# breakout_STM32F030F4P6.net
KiCad netlist of a schematic drawn in EAGLE
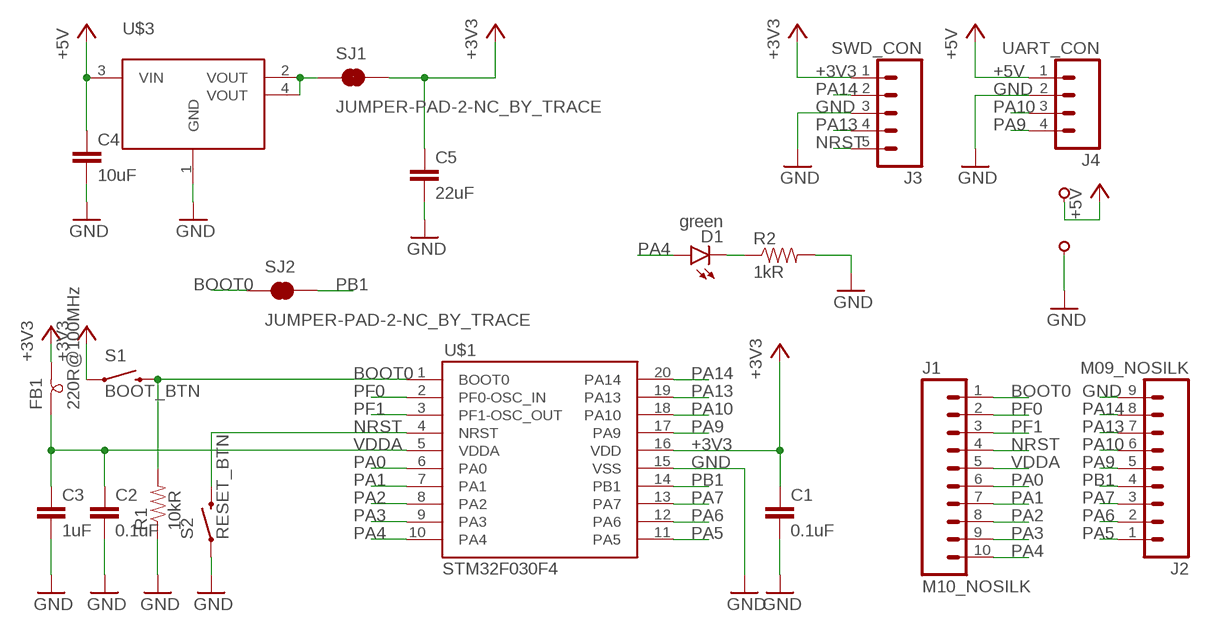
[diagram p0: schematic, sheet 1]

(export (version "E")
  (design (tool "Eeschema 10.0.6"))
  (components
    (comp (ref "C1")
      (value "0.1uF")
      (footprint "eagle-import:0805")
      (libsource (lib "eagle-import") (part "CAPACITOR0805"))
    )
    (comp (ref "C2")
      (value "0.1uF")
      (footprint "eagle-import:0805")
      (libsource (lib "eagle-import") (part "CAPACITOR0805"))
    )
    (comp (ref "C3")
      (value "1uF")
      (footprint "eagle-import:0805")
      (libsource (lib "eagle-import") (part "CAPACITOR0805"))
    )
    (comp (ref "C4")
      (value "10uF")
      (footprint "eagle-import:0805")
      (libsource (lib "eagle-import") (part "CAPACITOR0805"))
    )
    (comp (ref "C5")
      (value "22uF")
      (footprint "eagle-import:0805")
      (libsource (lib "eagle-import") (part "CAPACITOR0805"))
    )
    (comp (ref "D1")
      (value "green")
      (footprint "eagle-import:LED-805")
      (libsource (lib "eagle-import") (part "LED805"))
    )
    (comp (ref "FB1")
      (value "220R@100MHz")
      (footprint "eagle-import:0805")
      (libsource (lib "eagle-import") (part "FERRITE-BEAD0805"))
    )
    (comp (ref "J1")
      (value "M10_NOSILK")
      (footprint "eagle-import:M10_NOSILK")
      (libsource (lib "eagle-import") (part "M10_NOSILK"))
    )
    (comp (ref "J2")
      (value "M09_NOSILK")
      (footprint "eagle-import:M09_NOSILK")
      (libsource (lib "eagle-import") (part "M09_NOSILK"))
    )
    (comp (ref "J3")
      (value "SWD_CON")
      (footprint "eagle-import:M05_NOSILK_1SQ")
      (libsource (lib "eagle-import") (part "M05_NOSILK_1SQ"))
    )
    (comp (ref "J4")
      (value "UART_CON")
      (footprint "eagle-import:M04_NOSILK_1SQ")
      (libsource (lib "eagle-import") (part "M04_NOSILK_1SQ"))
    )
    (comp (ref "R1")
      (value "10kR")
      (footprint "eagle-import:0805")
      (libsource (lib "eagle-import") (part "RESISTOR0805"))
    )
    (comp (ref "R2")
      (value "1kR")
      (footprint "eagle-import:0805")
      (libsource (lib "eagle-import") (part "RESISTOR0805"))
    )
    (comp (ref "S1")
      (value "BOOT_BTN")
      (footprint "eagle-import:TACTILE-SWITCH-1101NE")
      (libsource (lib "eagle-import") (part "SWITCH-MOMENTARY-2-SMD-1101NE"))
    )
    (comp (ref "S2")
      (value "RESET_BTN")
      (footprint "eagle-import:TACTILE-SWITCH-1101NE")
      (libsource (lib "eagle-import") (part "SWITCH-MOMENTARY-2-SMD-1101NE"))
    )
    (comp (ref "SJ1")
      (value "JUMPER-PAD-2-NC_BY_TRACE")
      (footprint "eagle-import:PAD-JUMPER-2-NC_BY_TRACE_YES_SILK")
      (libsource (lib "eagle-import") (part "JUMPER-PAD-2-NC_BY_TRACE"))
    )
    (comp (ref "SJ2")
      (value "JUMPER-PAD-2-NC_BY_TRACE")
      (footprint "eagle-import:PAD-JUMPER-2-NC_BY_TRACE_YES_SILK")
      (libsource (lib "eagle-import") (part "JUMPER-PAD-2-NC_BY_TRACE"))
    )
    (comp (ref "U$1")
      (value "STM32F030F4")
      (footprint "eagle-import:TSSOP-20")
      (libsource (lib "eagle-import") (part "STM32F030F4"))
    )
    (comp (ref "U$2")
      (value "M01_1SQ")
      (footprint "eagle-import:M01_1SQ")
      (libsource (lib "eagle-import") (part "M01_1SQ"))
    )
    (comp (ref "U$3")
      (value "AMS1117_SOT223")
      (footprint "eagle-import:SOT223")
      (libsource (lib "eagle-import") (part "AMS1117_SOT223"))
    )
    (comp (ref "U$4")
      (value "M01_NOSILK")
      (footprint "eagle-import:M01_NOSILK")
      (libsource (lib "eagle-import") (part "M01_NOSILK"))
    )
  )
  (nets
    (net (code "1") (name "+3V3") (class "Default")
      (node (ref "C1") (pin "1") (pinfunction "1_1") (pintype "passive"))
      (node (ref "C5") (pin "1") (pinfunction "1_1") (pintype "passive"))
      (node (ref "FB1") (pin "2") (pinfunction "2_2") (pintype "passive"))
      (node (ref "J3") (pin "1") (pinfunction "1_1") (pintype "passive"))
      (node (ref "S1") (pin "1") (pinfunction "1_1") (pintype "passive"))
      (node (ref "SJ1") (pin "2") (pinfunction "2_2") (pintype "passive"))
      (node (ref "U$1") (pin "16") (pinfunction "VDD_16") (pintype "bidirectional"))
    )
    (net (code "2") (name "+5V") (class "Default")
      (node (ref "C4") (pin "1") (pinfunction "1_1") (pintype "passive"))
      (node (ref "J4") (pin "1") (pinfunction "1_1") (pintype "passive"))
      (node (ref "U$2") (pin "1") (pinfunction "1_1") (pintype "bidirectional"))
      (node (ref "U$3") (pin "3") (pinfunction "VIN_3") (pintype "bidirectional"))
    )
    (net (code "3") (name "/BOOT0") (class "Default")
      (node (ref "J1") (pin "1") (pinfunction "1_1") (pintype "passive"))
      (node (ref "R1") (pin "2") (pinfunction "2_2") (pintype "passive"))
      (node (ref "S1") (pin "2") (pinfunction "2_2") (pintype "passive"))
      (node (ref "SJ2") (pin "1") (pinfunction "1_1") (pintype "passive"))
      (node (ref "U$1") (pin "1") (pinfunction "BOOT0_1") (pintype "bidirectional"))
    )
    (net (code "4") (name "/NRST") (class "Default")
      (node (ref "J1") (pin "4") (pinfunction "4_4") (pintype "passive"))
      (node (ref "J3") (pin "5") (pinfunction "5_5") (pintype "passive"))
      (node (ref "S2") (pin "2") (pinfunction "2_2") (pintype "passive"))
      (node (ref "U$1") (pin "4") (pinfunction "NRST_4") (pintype "bidirectional"))
    )
    (net (code "5") (name "/PA0") (class "Default")
      (node (ref "J1") (pin "6") (pinfunction "6_6") (pintype "passive"))
      (node (ref "U$1") (pin "6") (pinfunction "PA0_6") (pintype "bidirectional"))
    )
    (net (code "6") (name "/PA1") (class "Default")
      (node (ref "J1") (pin "7") (pinfunction "7_7") (pintype "passive"))
      (node (ref "U$1") (pin "7") (pinfunction "PA1_7") (pintype "bidirectional"))
    )
    (net (code "7") (name "/PA2") (class "Default")
      (node (ref "J1") (pin "8") (pinfunction "8_8") (pintype "passive"))
      (node (ref "U$1") (pin "8") (pinfunction "PA2_8") (pintype "bidirectional"))
    )
    (net (code "8") (name "/PA3") (class "Default")
      (node (ref "J1") (pin "9") (pinfunction "9_9") (pintype "passive"))
      (node (ref "U$1") (pin "9") (pinfunction "PA3_9") (pintype "bidirectional"))
    )
    (net (code "9") (name "/PA4") (class "Default")
      (node (ref "D1") (pin "A") (pinfunction "A_A") (pintype "passive"))
      (node (ref "J1") (pin "10") (pinfunction "10_10") (pintype "passive"))
      (node (ref "U$1") (pin "10") (pinfunction "PA4_10") (pintype "bidirectional"))
    )
    (net (code "10") (name "/PA5") (class "Default")
      (node (ref "J2") (pin "1") (pinfunction "1_1") (pintype "passive"))
      (node (ref "U$1") (pin "11") (pinfunction "PA5_11") (pintype "bidirectional"))
    )
    (net (code "11") (name "/PA6") (class "Default")
      (node (ref "J2") (pin "2") (pinfunction "2_2") (pintype "passive"))
      (node (ref "U$1") (pin "12") (pinfunction "PA6_12") (pintype "bidirectional"))
    )
    (net (code "12") (name "/PA7") (class "Default")
      (node (ref "J2") (pin "3") (pinfunction "3_3") (pintype "passive"))
      (node (ref "U$1") (pin "13") (pinfunction "PA7_13") (pintype "bidirectional"))
    )
    (net (code "13") (name "/PA9") (class "Default")
      (node (ref "J2") (pin "5") (pinfunction "5_5") (pintype "passive"))
      (node (ref "J4") (pin "4") (pinfunction "4_4") (pintype "passive"))
      (node (ref "U$1") (pin "17") (pinfunction "PA9_17") (pintype "bidirectional"))
    )
    (net (code "14") (name "/PA10") (class "Default")
      (node (ref "J2") (pin "6") (pinfunction "6_6") (pintype "passive"))
      (node (ref "J4") (pin "3") (pinfunction "3_3") (pintype "passive"))
      (node (ref "U$1") (pin "18") (pinfunction "PA10_18") (pintype "bidirectional"))
    )
    (net (code "15") (name "/PA13") (class "Default")
      (node (ref "J2") (pin "7") (pinfunction "7_7") (pintype "passive"))
      (node (ref "J3") (pin "4") (pinfunction "4_4") (pintype "passive"))
      (node (ref "U$1") (pin "19") (pinfunction "PA13_19") (pintype "bidirectional"))
    )
    (net (code "16") (name "/PA14") (class "Default")
      (node (ref "J2") (pin "8") (pinfunction "8_8") (pintype "passive"))
      (node (ref "J3") (pin "2") (pinfunction "2_2") (pintype "passive"))
      (node (ref "U$1") (pin "20") (pinfunction "PA14_20") (pintype "bidirectional"))
    )
    (net (code "17") (name "/PB1") (class "Default")
      (node (ref "J2") (pin "4") (pinfunction "4_4") (pintype "passive"))
      (node (ref "SJ2") (pin "2") (pinfunction "2_2") (pintype "passive"))
      (node (ref "U$1") (pin "14") (pinfunction "PB1_14") (pintype "bidirectional"))
    )
    (net (code "18") (name "/PF0") (class "Default")
      (node (ref "J1") (pin "2") (pinfunction "2_2") (pintype "passive"))
      (node (ref "U$1") (pin "2") (pinfunction "PF0-OSC_IN_2") (pintype "bidirectional"))
    )
    (net (code "19") (name "/PF1") (class "Default")
      (node (ref "J1") (pin "3") (pinfunction "3_3") (pintype "passive"))
      (node (ref "U$1") (pin "3") (pinfunction "PF1-OSC_OUT_3") (pintype "bidirectional"))
    )
    (net (code "20") (name "/VDDA") (class "Default")
      (node (ref "C2") (pin "1") (pinfunction "1_1") (pintype "passive"))
      (node (ref "C3") (pin "1") (pinfunction "1_1") (pintype "passive"))
      (node (ref "FB1") (pin "1") (pinfunction "1_1") (pintype "passive"))
      (node (ref "J1") (pin "5") (pinfunction "5_5") (pintype "passive"))
      (node (ref "U$1") (pin "5") (pinfunction "VDDA_5") (pintype "bidirectional"))
    )
    (net (code "21") (name "GND") (class "Default")
      (node (ref "C1") (pin "2") (pinfunction "2_2") (pintype "passive"))
      (node (ref "C2") (pin "2") (pinfunction "2_2") (pintype "passive"))
      (node (ref "C3") (pin "2") (pinfunction "2_2") (pintype "passive"))
      (node (ref "C4") (pin "2") (pinfunction "2_2") (pintype "passive"))
      (node (ref "C5") (pin "2") (pinfunction "2_2") (pintype "passive"))
      (node (ref "J2") (pin "9") (pinfunction "9_9") (pintype "passive"))
      (node (ref "J3") (pin "3") (pinfunction "3_3") (pintype "passive"))
      (node (ref "J4") (pin "2") (pinfunction "2_2") (pintype "passive"))
      (node (ref "R1") (pin "1") (pinfunction "1_1") (pintype "passive"))
      (node (ref "R2") (pin "2") (pinfunction "2_2") (pintype "passive"))
      (node (ref "S2") (pin "1") (pinfunction "1_1") (pintype "passive"))
      (node (ref "U$1") (pin "15") (pinfunction "VSS_15") (pintype "bidirectional"))
      (node (ref "U$3") (pin "1") (pinfunction "GND_1") (pintype "bidirectional"))
      (node (ref "U$4") (pin "1") (pinfunction "1_1") (pintype "bidirectional"))
    )
    (net (code "22") (name "Net-(D1-PadC)") (class "Default")
      (node (ref "D1") (pin "C") (pinfunction "C_C") (pintype "passive"))
      (node (ref "R2") (pin "1") (pinfunction "1_1") (pintype "passive"))
    )
    (net (code "23") (name "Net-(SJ1-Pad1)") (class "Default")
      (node (ref "SJ1") (pin "1") (pinfunction "1_1") (pintype "passive"))
      (node (ref "U$3") (pin "2") (pinfunction "VOUT_2") (pintype "bidirectional"))
      (node (ref "U$3") (pin "4") (pinfunction "VOUT_4") (pintype "bidirectional"))
    )
  )
)
